# LCs.net
KiCad netlist of a schematic drawn in Altium Designer
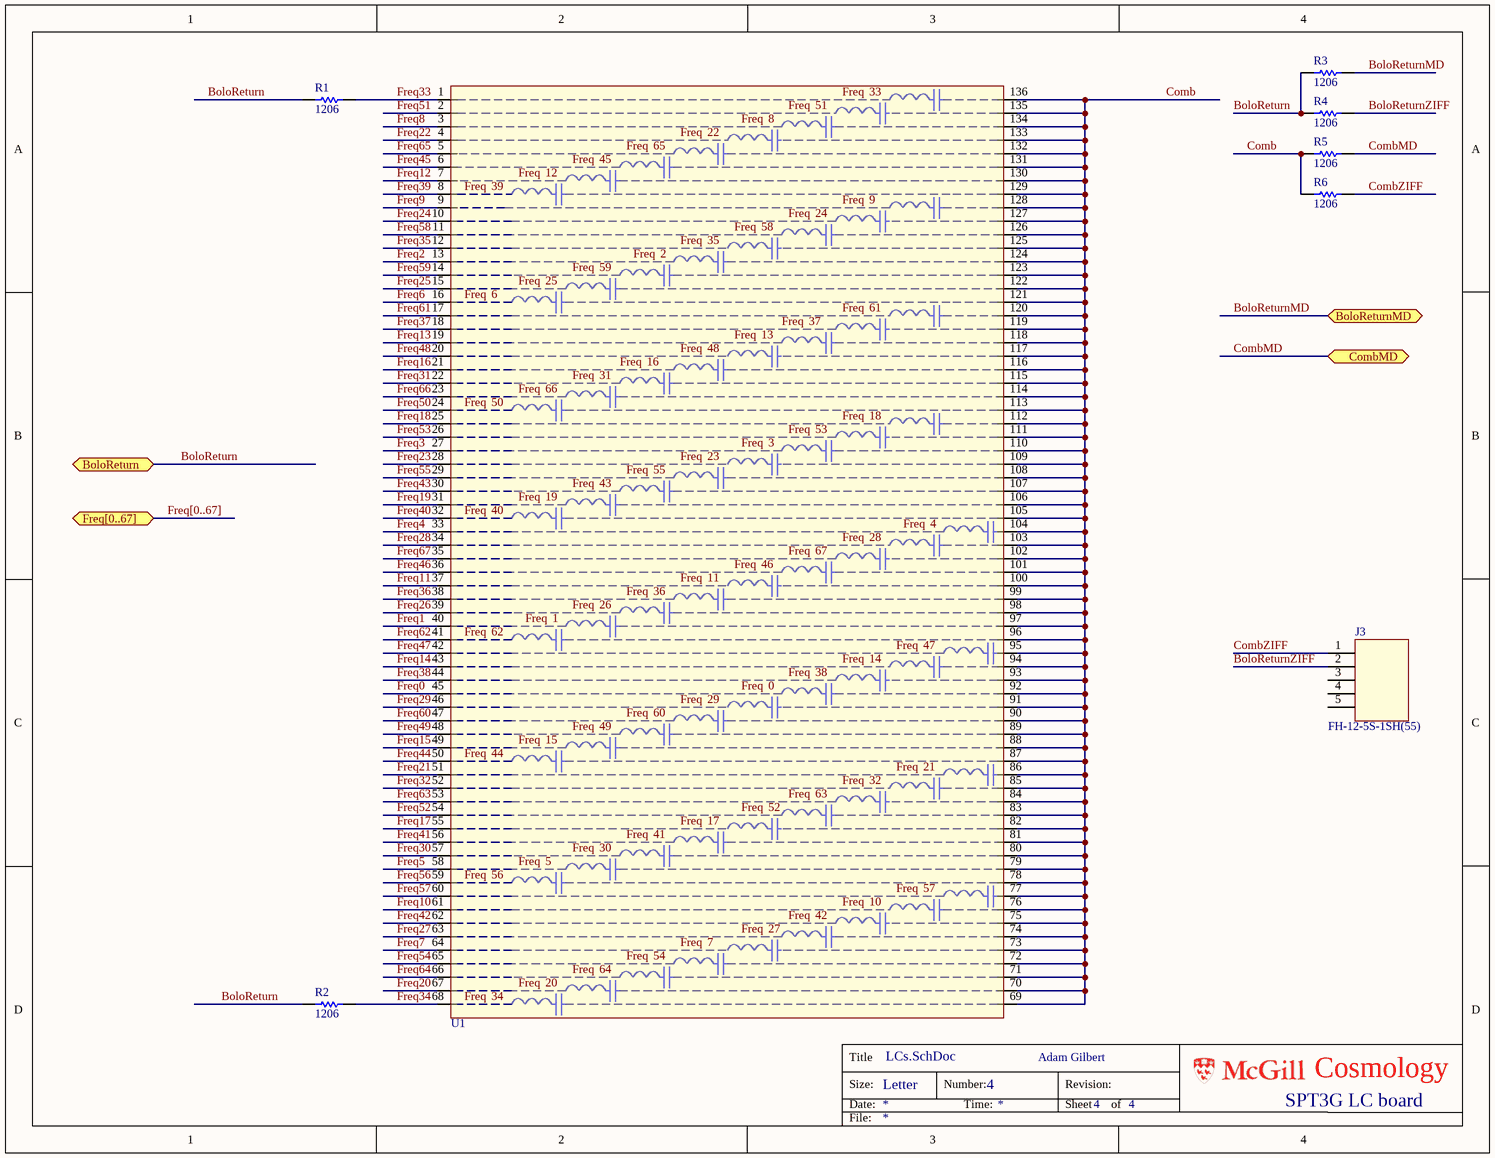
[diagram p0: LCs.SchDoc]

(export (version "E")
  (design (tool "Eeschema 10.0.6"))
  (components
    (comp (ref "J3")
      (value "FH-12-5S-1SH(55)")
      (footprint "FH-12-5S-1SH(55)")
      (libsource (lib "SPT3G_LCBoard") (part "FH-12-5S-1SH(55)"))
    )
    (comp (ref "R1")
      (value "Res1206")
      (footprint "1206")
      (description "Resistor")
      (libsource (lib "SPT3G_LCBoard") (part "Res1206"))
    )
    (comp (ref "R2")
      (value "Res1206")
      (footprint "1206")
      (description "Resistor")
      (libsource (lib "SPT3G_LCBoard") (part "Res1206"))
    )
    (comp (ref "R3")
      (value "Res1206")
      (footprint "1206")
      (description "Resistor")
      (libsource (lib "SPT3G_LCBoard") (part "Res1206"))
    )
    (comp (ref "R4")
      (value "Res1206")
      (footprint "1206")
      (description "Resistor")
      (libsource (lib "SPT3G_LCBoard") (part "Res1206"))
    )
    (comp (ref "R5")
      (value "Res1206")
      (footprint "1206")
      (description "Resistor")
      (libsource (lib "SPT3G_LCBoard") (part "Res1206"))
    )
    (comp (ref "R6")
      (value "Res1206")
      (footprint "1206")
      (description "Resistor")
      (libsource (lib "SPT3G_LCBoard") (part "Res1206"))
    )
    (comp (ref "U1")
      (value "LC68_wafer")
      (footprint "68xLC")
      (description "Gold bonded integrated LC")
      (libsource (lib "SPT3G_LCBoard") (part "LC68Wafer"))
    )
  )
  (nets
    (net (code "1") (name "/BoloReturn") (class "Default")
      (node (ref "R1") (pin "1") (pinfunction "1_1") (pintype "passive"))
      (node (ref "R2") (pin "1") (pinfunction "1_1") (pintype "passive"))
      (node (ref "R3") (pin "1") (pinfunction "1_1") (pintype "passive"))
      (node (ref "R4") (pin "1") (pinfunction "1_1") (pintype "passive"))
    )
    (net (code "2") (name "/BoloReturnMD") (class "Default")
      (node (ref "R3") (pin "2") (pinfunction "2_2") (pintype "passive"))
    )
    (net (code "3") (name "/BoloReturnZIFF") (class "Default")
      (node (ref "J3") (pin "2") (pinfunction "2_2") (pintype "passive"))
      (node (ref "R4") (pin "2") (pinfunction "2_2") (pintype "passive"))
    )
    (net (code "4") (name "/Comb") (class "Default")
      (node (ref "R5") (pin "1") (pinfunction "1_1") (pintype "passive"))
      (node (ref "R6") (pin "1") (pinfunction "1_1") (pintype "passive"))
      (node (ref "U1") (pin "100") (pinfunction "100_100") (pintype "passive"))
      (node (ref "U1") (pin "101") (pinfunction "101_101") (pintype "passive"))
      (node (ref "U1") (pin "102") (pinfunction "102_102") (pintype "passive"))
      (node (ref "U1") (pin "103") (pinfunction "103_103") (pintype "passive"))
      (node (ref "U1") (pin "104") (pinfunction "104_104") (pintype "passive"))
      (node (ref "U1") (pin "105") (pinfunction "105_105") (pintype "passive"))
      (node (ref "U1") (pin "106") (pinfunction "106_106") (pintype "passive"))
      (node (ref "U1") (pin "107") (pinfunction "107_107") (pintype "passive"))
      (node (ref "U1") (pin "108") (pinfunction "108_108") (pintype "passive"))
      (node (ref "U1") (pin "109") (pinfunction "109_109") (pintype "passive"))
      (node (ref "U1") (pin "110") (pinfunction "110_110") (pintype "passive"))
      (node (ref "U1") (pin "111") (pinfunction "111_111") (pintype "passive"))
      (node (ref "U1") (pin "112") (pinfunction "112_112") (pintype "passive"))
      (node (ref "U1") (pin "113") (pinfunction "113_113") (pintype "passive"))
      (node (ref "U1") (pin "114") (pinfunction "114_114") (pintype "passive"))
      (node (ref "U1") (pin "115") (pinfunction "115_115") (pintype "passive"))
      (node (ref "U1") (pin "116") (pinfunction "116_116") (pintype "passive"))
      (node (ref "U1") (pin "117") (pinfunction "117_117") (pintype "passive"))
      (node (ref "U1") (pin "118") (pinfunction "118_118") (pintype "passive"))
      (node (ref "U1") (pin "119") (pinfunction "119_119") (pintype "passive"))
      (node (ref "U1") (pin "120") (pinfunction "120_120") (pintype "passive"))
      (node (ref "U1") (pin "121") (pinfunction "121_121") (pintype "passive"))
      (node (ref "U1") (pin "122") (pinfunction "122_122") (pintype "passive"))
      (node (ref "U1") (pin "123") (pinfunction "123_123") (pintype "passive"))
      (node (ref "U1") (pin "124") (pinfunction "124_124") (pintype "passive"))
      (node (ref "U1") (pin "125") (pinfunction "125_125") (pintype "passive"))
      (node (ref "U1") (pin "126") (pinfunction "126_126") (pintype "passive"))
      (node (ref "U1") (pin "127") (pinfunction "127_127") (pintype "passive"))
      (node (ref "U1") (pin "128") (pinfunction "128_128") (pintype "passive"))
      (node (ref "U1") (pin "129") (pinfunction "129_129") (pintype "passive"))
      (node (ref "U1") (pin "130") (pinfunction "130_130") (pintype "passive"))
      (node (ref "U1") (pin "131") (pinfunction "131_131") (pintype "passive"))
      (node (ref "U1") (pin "132") (pinfunction "132_132") (pintype "passive"))
      (node (ref "U1") (pin "133") (pinfunction "133_133") (pintype "passive"))
      (node (ref "U1") (pin "134") (pinfunction "134_134") (pintype "passive"))
      (node (ref "U1") (pin "135") (pinfunction "135_135") (pintype "passive"))
      (node (ref "U1") (pin "136") (pinfunction "136_136") (pintype "passive"))
      (node (ref "U1") (pin "69") (pinfunction "69_69") (pintype "passive"))
      (node (ref "U1") (pin "70") (pinfunction "70_70") (pintype "passive"))
      (node (ref "U1") (pin "71") (pinfunction "71_71") (pintype "passive"))
      (node (ref "U1") (pin "72") (pinfunction "72_72") (pintype "passive"))
      (node (ref "U1") (pin "73") (pinfunction "73_73") (pintype "passive"))
      (node (ref "U1") (pin "74") (pinfunction "74_74") (pintype "passive"))
      (node (ref "U1") (pin "75") (pinfunction "75_75") (pintype "passive"))
      (node (ref "U1") (pin "76") (pinfunction "76_76") (pintype "passive"))
      (node (ref "U1") (pin "77") (pinfunction "77_77") (pintype "passive"))
      (node (ref "U1") (pin "78") (pinfunction "78_78") (pintype "passive"))
      (node (ref "U1") (pin "79") (pinfunction "79_79") (pintype "passive"))
      (node (ref "U1") (pin "80") (pinfunction "80_80") (pintype "passive"))
      (node (ref "U1") (pin "81") (pinfunction "81_81") (pintype "passive"))
      (node (ref "U1") (pin "82") (pinfunction "82_82") (pintype "passive"))
      (node (ref "U1") (pin "83") (pinfunction "83_83") (pintype "passive"))
      (node (ref "U1") (pin "84") (pinfunction "84_84") (pintype "passive"))
      (node (ref "U1") (pin "85") (pinfunction "85_85") (pintype "passive"))
      (node (ref "U1") (pin "86") (pinfunction "86_86") (pintype "passive"))
      (node (ref "U1") (pin "87") (pinfunction "87_87") (pintype "passive"))
      (node (ref "U1") (pin "88") (pinfunction "88_88") (pintype "passive"))
      (node (ref "U1") (pin "89") (pinfunction "89_89") (pintype "passive"))
      (node (ref "U1") (pin "90") (pinfunction "90_90") (pintype "passive"))
      (node (ref "U1") (pin "91") (pinfunction "91_91") (pintype "passive"))
      (node (ref "U1") (pin "92") (pinfunction "92_92") (pintype "passive"))
      (node (ref "U1") (pin "93") (pinfunction "93_93") (pintype "passive"))
      (node (ref "U1") (pin "94") (pinfunction "94_94") (pintype "passive"))
      (node (ref "U1") (pin "95") (pinfunction "95_95") (pintype "passive"))
      (node (ref "U1") (pin "96") (pinfunction "96_96") (pintype "passive"))
      (node (ref "U1") (pin "97") (pinfunction "97_97") (pintype "passive"))
      (node (ref "U1") (pin "98") (pinfunction "98_98") (pintype "passive"))
      (node (ref "U1") (pin "99") (pinfunction "99_99") (pintype "passive"))
    )
    (net (code "5") (name "/CombMD") (class "Default")
      (node (ref "R5") (pin "2") (pinfunction "2_2") (pintype "passive"))
    )
    (net (code "6") (name "/CombZIFF") (class "Default")
      (node (ref "J3") (pin "1") (pinfunction "1_1") (pintype "passive"))
      (node (ref "R6") (pin "2") (pinfunction "2_2") (pintype "passive"))
    )
    (net (code "7") (name "/Freq0") (class "Default")
      (node (ref "U1") (pin "45") (pinfunction "45_45") (pintype "passive"))
    )
    (net (code "8") (name "/Freq1") (class "Default")
      (node (ref "U1") (pin "40") (pinfunction "40_40") (pintype "passive"))
    )
    (net (code "9") (name "/Freq2") (class "Default")
      (node (ref "U1") (pin "13") (pinfunction "13_13") (pintype "passive"))
    )
    (net (code "10") (name "/Freq3") (class "Default")
      (node (ref "U1") (pin "27") (pinfunction "27_27") (pintype "passive"))
    )
    (net (code "11") (name "/Freq4") (class "Default")
      (node (ref "U1") (pin "33") (pinfunction "33_33") (pintype "passive"))
    )
    (net (code "12") (name "/Freq5") (class "Default")
      (node (ref "U1") (pin "58") (pinfunction "58_58") (pintype "passive"))
    )
    (net (code "13") (name "/Freq6") (class "Default")
      (node (ref "U1") (pin "16") (pinfunction "16_16") (pintype "passive"))
    )
    (net (code "14") (name "/Freq7") (class "Default")
      (node (ref "U1") (pin "64") (pinfunction "64_64") (pintype "passive"))
    )
    (net (code "15") (name "/Freq8") (class "Default")
      (node (ref "U1") (pin "3") (pinfunction "3_3") (pintype "passive"))
    )
    (net (code "16") (name "/Freq9") (class "Default")
      (node (ref "U1") (pin "9") (pinfunction "9_9") (pintype "passive"))
    )
    (net (code "17") (name "/Freq10") (class "Default")
      (node (ref "U1") (pin "61") (pinfunction "61_61") (pintype "passive"))
    )
    (net (code "18") (name "/Freq11") (class "Default")
      (node (ref "U1") (pin "37") (pinfunction "37_37") (pintype "passive"))
    )
    (net (code "19") (name "/Freq12") (class "Default")
      (node (ref "U1") (pin "7") (pinfunction "7_7") (pintype "passive"))
    )
    (net (code "20") (name "/Freq13") (class "Default")
      (node (ref "U1") (pin "19") (pinfunction "19_19") (pintype "passive"))
    )
    (net (code "21") (name "/Freq14") (class "Default")
      (node (ref "U1") (pin "43") (pinfunction "43_43") (pintype "passive"))
    )
    (net (code "22") (name "/Freq15") (class "Default")
      (node (ref "U1") (pin "49") (pinfunction "49_49") (pintype "passive"))
    )
    (net (code "23") (name "/Freq16") (class "Default")
      (node (ref "U1") (pin "21") (pinfunction "21_21") (pintype "passive"))
    )
    (net (code "24") (name "/Freq17") (class "Default")
      (node (ref "U1") (pin "55") (pinfunction "55_55") (pintype "passive"))
    )
    (net (code "25") (name "/Freq18") (class "Default")
      (node (ref "U1") (pin "25") (pinfunction "25_25") (pintype "passive"))
    )
    (net (code "26") (name "/Freq19") (class "Default")
      (node (ref "U1") (pin "31") (pinfunction "31_31") (pintype "passive"))
    )
    (net (code "27") (name "/Freq20") (class "Default")
      (node (ref "U1") (pin "67") (pinfunction "67_67") (pintype "passive"))
    )
    (net (code "28") (name "/Freq21") (class "Default")
      (node (ref "U1") (pin "51") (pinfunction "51_51") (pintype "passive"))
    )
    (net (code "29") (name "/Freq22") (class "Default")
      (node (ref "U1") (pin "4") (pinfunction "4_4") (pintype "passive"))
    )
    (net (code "30") (name "/Freq23") (class "Default")
      (node (ref "U1") (pin "28") (pinfunction "28_28") (pintype "passive"))
    )
    (net (code "31") (name "/Freq24") (class "Default")
      (node (ref "U1") (pin "10") (pinfunction "10_10") (pintype "passive"))
    )
    (net (code "32") (name "/Freq25") (class "Default")
      (node (ref "U1") (pin "15") (pinfunction "15_15") (pintype "passive"))
    )
    (net (code "33") (name "/Freq26") (class "Default")
      (node (ref "U1") (pin "39") (pinfunction "39_39") (pintype "passive"))
    )
    (net (code "34") (name "/Freq27") (class "Default")
      (node (ref "U1") (pin "63") (pinfunction "63_63") (pintype "passive"))
    )
    (net (code "35") (name "/Freq28") (class "Default")
      (node (ref "U1") (pin "34") (pinfunction "34_34") (pintype "passive"))
    )
    (net (code "36") (name "/Freq29") (class "Default")
      (node (ref "U1") (pin "46") (pinfunction "46_46") (pintype "passive"))
    )
    (net (code "37") (name "/Freq30") (class "Default")
      (node (ref "U1") (pin "57") (pinfunction "57_57") (pintype "passive"))
    )
    (net (code "38") (name "/Freq31") (class "Default")
      (node (ref "U1") (pin "22") (pinfunction "22_22") (pintype "passive"))
    )
    (net (code "39") (name "/Freq32") (class "Default")
      (node (ref "U1") (pin "52") (pinfunction "52_52") (pintype "passive"))
    )
    (net (code "40") (name "/Freq33") (class "Default")
      (node (ref "R1") (pin "2") (pinfunction "2_2") (pintype "passive"))
      (node (ref "U1") (pin "1") (pinfunction "1_1") (pintype "passive"))
    )
    (net (code "41") (name "/Freq34") (class "Default")
      (node (ref "R2") (pin "2") (pinfunction "2_2") (pintype "passive"))
      (node (ref "U1") (pin "68") (pinfunction "68_68") (pintype "passive"))
    )
    (net (code "42") (name "/Freq35") (class "Default")
      (node (ref "U1") (pin "12") (pinfunction "12_12") (pintype "passive"))
    )
    (net (code "43") (name "/Freq36") (class "Default")
      (node (ref "U1") (pin "38") (pinfunction "38_38") (pintype "passive"))
    )
    (net (code "44") (name "/Freq37") (class "Default")
      (node (ref "U1") (pin "18") (pinfunction "18_18") (pintype "passive"))
    )
    (net (code "45") (name "/Freq38") (class "Default")
      (node (ref "U1") (pin "44") (pinfunction "44_44") (pintype "passive"))
    )
    (net (code "46") (name "/Freq39") (class "Default")
      (node (ref "U1") (pin "8") (pinfunction "8_8") (pintype "passive"))
    )
    (net (code "47") (name "/Freq40") (class "Default")
      (node (ref "U1") (pin "32") (pinfunction "32_32") (pintype "passive"))
    )
    (net (code "48") (name "/Freq41") (class "Default")
      (node (ref "U1") (pin "56") (pinfunction "56_56") (pintype "passive"))
    )
    (net (code "49") (name "/Freq42") (class "Default")
      (node (ref "U1") (pin "62") (pinfunction "62_62") (pintype "passive"))
    )
    (net (code "50") (name "/Freq43") (class "Default")
      (node (ref "U1") (pin "30") (pinfunction "30_30") (pintype "passive"))
    )
    (net (code "51") (name "/Freq44") (class "Default")
      (node (ref "U1") (pin "50") (pinfunction "50_50") (pintype "passive"))
    )
    (net (code "52") (name "/Freq45") (class "Default")
      (node (ref "U1") (pin "6") (pinfunction "6_6") (pintype "passive"))
    )
    (net (code "53") (name "/Freq46") (class "Default")
      (node (ref "U1") (pin "36") (pinfunction "36_36") (pintype "passive"))
    )
    (net (code "54") (name "/Freq47") (class "Default")
      (node (ref "U1") (pin "42") (pinfunction "42_42") (pintype "passive"))
    )
    (net (code "55") (name "/Freq48") (class "Default")
      (node (ref "U1") (pin "20") (pinfunction "20_20") (pintype "passive"))
    )
    (net (code "56") (name "/Freq49") (class "Default")
      (node (ref "U1") (pin "48") (pinfunction "48_48") (pintype "passive"))
    )
    (net (code "57") (name "/Freq50") (class "Default")
      (node (ref "U1") (pin "24") (pinfunction "24_24") (pintype "passive"))
    )
    (net (code "58") (name "/Freq51") (class "Default")
      (node (ref "U1") (pin "2") (pinfunction "2_2") (pintype "passive"))
    )
    (net (code "59") (name "/Freq52") (class "Default")
      (node (ref "U1") (pin "54") (pinfunction "54_54") (pintype "passive"))
    )
    (net (code "60") (name "/Freq53") (class "Default")
      (node (ref "U1") (pin "26") (pinfunction "26_26") (pintype "passive"))
    )
    (net (code "61") (name "/Freq54") (class "Default")
      (node (ref "U1") (pin "65") (pinfunction "65_65") (pintype "passive"))
    )
    (net (code "62") (name "/Freq55") (class "Default")
      (node (ref "U1") (pin "29") (pinfunction "29_29") (pintype "passive"))
    )
    (net (code "63") (name "/Freq56") (class "Default")
      (node (ref "U1") (pin "59") (pinfunction "59_59") (pintype "passive"))
    )
    (net (code "64") (name "/Freq57") (class "Default")
      (node (ref "U1") (pin "60") (pinfunction "60_60") (pintype "passive"))
    )
    (net (code "65") (name "/Freq58") (class "Default")
      (node (ref "U1") (pin "11") (pinfunction "11_11") (pintype "passive"))
    )
    (net (code "66") (name "/Freq59") (class "Default")
      (node (ref "U1") (pin "14") (pinfunction "14_14") (pintype "passive"))
    )
    (net (code "67") (name "/Freq60") (class "Default")
      (node (ref "U1") (pin "47") (pinfunction "47_47") (pintype "passive"))
    )
    (net (code "68") (name "/Freq61") (class "Default")
      (node (ref "U1") (pin "17") (pinfunction "17_17") (pintype "passive"))
    )
    (net (code "69") (name "/Freq62") (class "Default")
      (node (ref "U1") (pin "41") (pinfunction "41_41") (pintype "passive"))
    )
    (net (code "70") (name "/Freq63") (class "Default")
      (node (ref "U1") (pin "53") (pinfunction "53_53") (pintype "passive"))
    )
    (net (code "71") (name "/Freq64") (class "Default")
      (node (ref "U1") (pin "66") (pinfunction "66_66") (pintype "passive"))
    )
    (net (code "72") (name "/Freq65") (class "Default")
      (node (ref "U1") (pin "5") (pinfunction "5_5") (pintype "passive"))
    )
    (net (code "73") (name "/Freq66") (class "Default")
      (node (ref "U1") (pin "23") (pinfunction "23_23") (pintype "passive"))
    )
    (net (code "74") (name "/Freq67") (class "Default")
      (node (ref "U1") (pin "35") (pinfunction "35_35") (pintype "passive"))
    )
    (net (code "76") (name "unconnected-(J3-Pad3)") (class "Default")
      (node (ref "J3") (pin "3") (pinfunction "3_3") (pintype "passive"))
    )
    (net (code "77") (name "unconnected-(J3-Pad4)") (class "Default")
      (node (ref "J3") (pin "4") (pinfunction "4_4") (pintype "passive"))
    )
    (net (code "78") (name "unconnected-(J3-Pad5)") (class "Default")
      (node (ref "J3") (pin "5") (pinfunction "5_5") (pintype "passive"))
    )
  )
)
